# homie-wemos.net
KiCad netlist of a schematic drawn in EAGLE
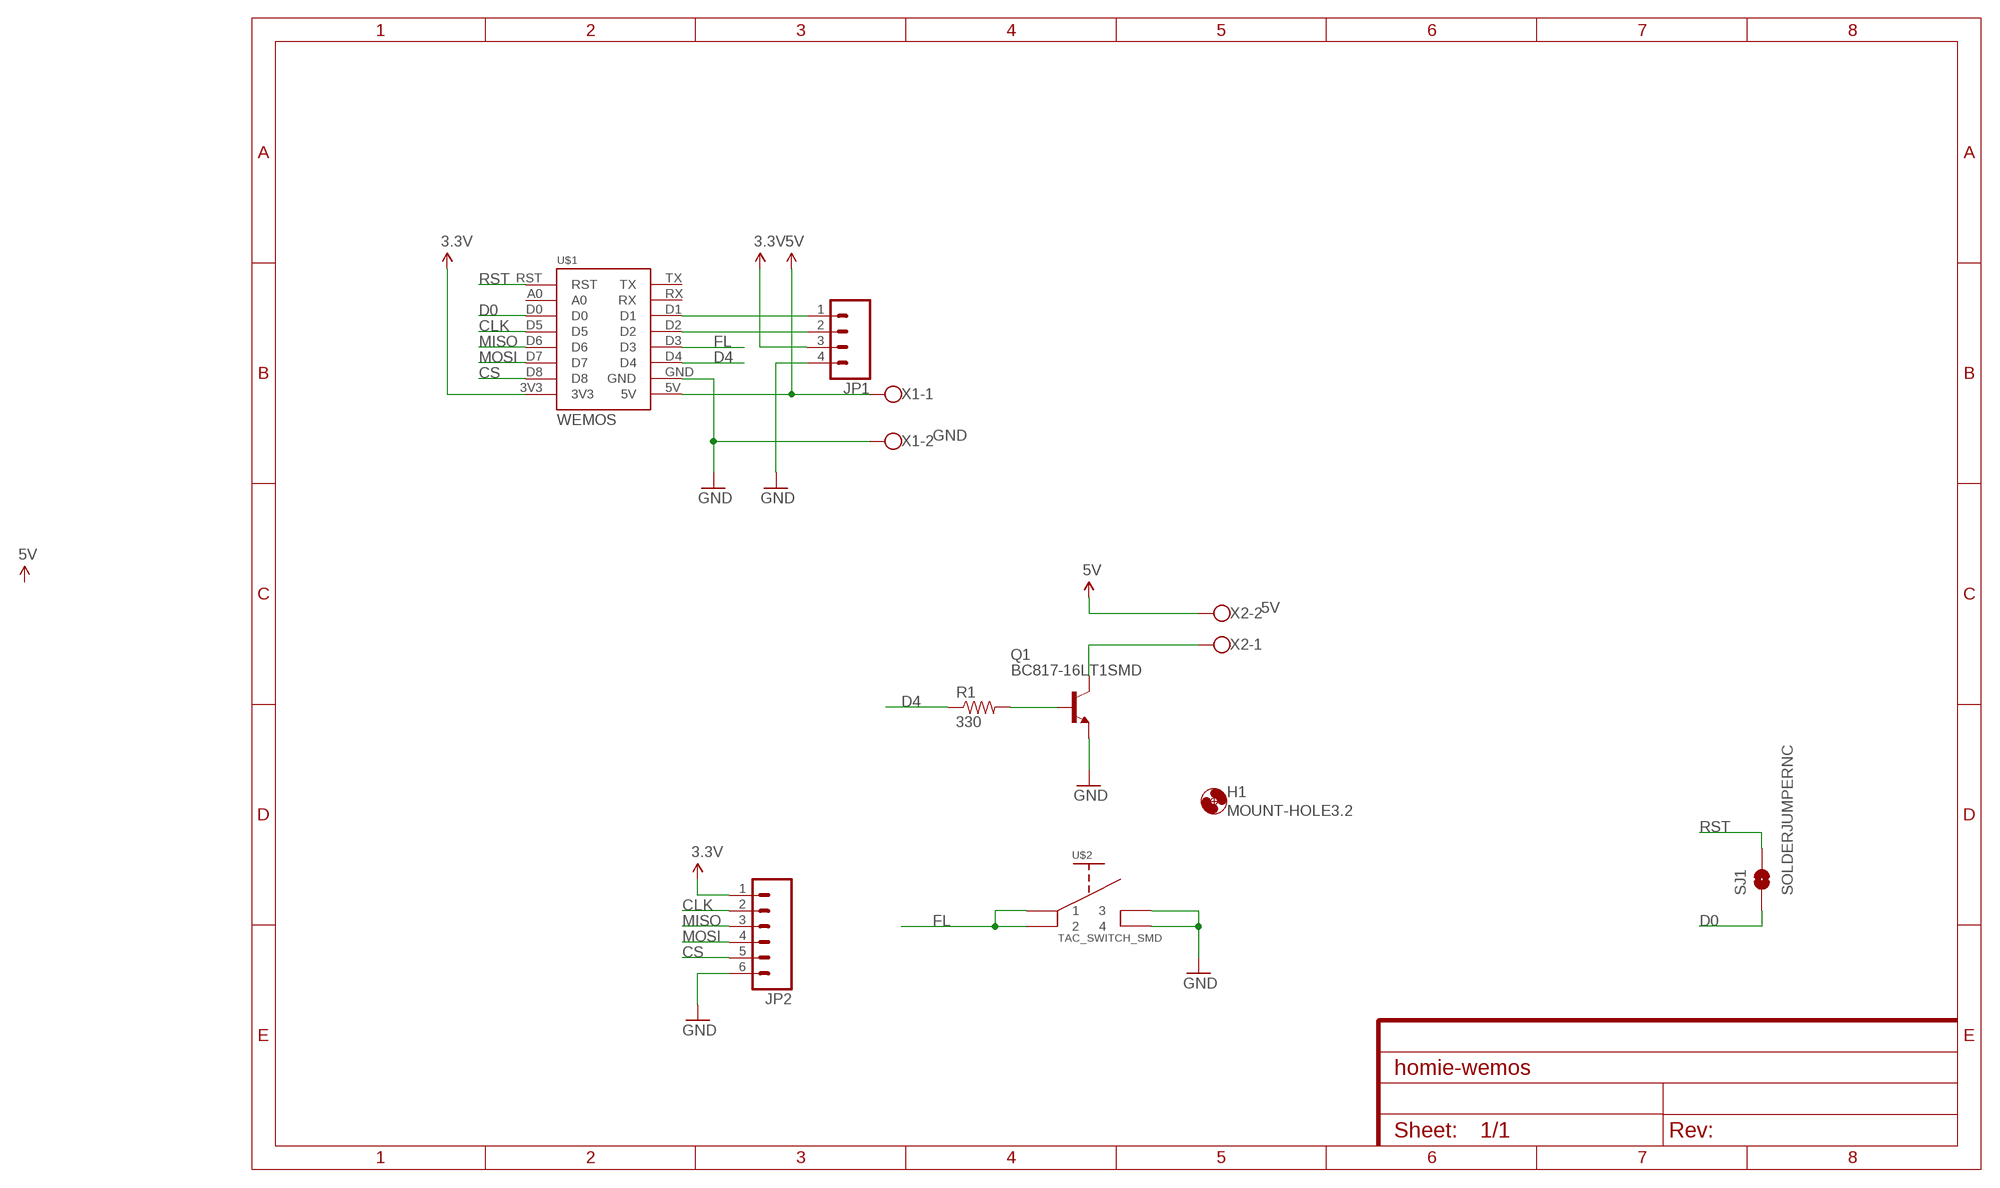
[diagram p0: schematic, sheet 1]

(export (version "E")
  (design (tool "Eeschema 10.0.6"))
  (components
    (comp (ref "H1")
      (value "MOUNT-HOLE3.2")
      (footprint "eagle-import:3,2")
      (libsource (lib "eagle-import") (part "MOUNT-HOLE3.2"))
    )
    (comp (ref "JP1")
      (value "M04LOCK_LONGPADS")
      (footprint "eagle-import:1X04_LOCK_LONGPADS")
      (libsource (lib "eagle-import") (part "M04LOCK_LONGPADS"))
    )
    (comp (ref "JP2")
      (value "M06LOCK_LONGPADS")
      (footprint "eagle-import:1X06_LOCK_LONGPADS")
      (libsource (lib "eagle-import") (part "M06LOCK_LONGPADS"))
    )
    (comp (ref "Q1")
      (value "BC817-16LT1SMD")
      (footprint "eagle-import:SOT23-BEC")
      (libsource (lib "eagle-import") (part "BC817SMD-16LT1"))
    )
    (comp (ref "R1")
      (value "330")
      (footprint "eagle-import:0603-RES")
      (libsource (lib "eagle-import") (part "RESISTOR0603-RES"))
    )
    (comp (ref "SJ1")
      (value "SOLDERJUMPERNC")
      (footprint "eagle-import:SJ_2S")
      (libsource (lib "eagle-import") (part "SOLDERJUMPERNC"))
    )
    (comp (ref "U$1")
      (value "WEMOS")
      (footprint "eagle-import:WEMOS")
      (libsource (lib "eagle-import") (part "WEMOS"))
    )
    (comp (ref "U$2")
      (value "TS-017A")
      (footprint "eagle-import:TS-017ASMD")
      (libsource (lib "eagle-import") (part "TS-017A"))
    )
    (comp (ref "X1")
      (value "W237-102")
      (footprint "eagle-import:W237-102")
      (fields (field (name "MPN") "237-102"))
      (libsource (lib "eagle-import") (part "W237-102"))
    )
    (comp (ref "X2")
      (value "W237-102")
      (footprint "eagle-import:W237-102")
      (fields (field (name "MPN") "237-102"))
      (libsource (lib "eagle-import") (part "W237-102"))
    )
  )
  (nets
    (net (code "1") (name "/CLK") (class "Default")
      (node (ref "JP2") (pin "2") (pinfunction "2_2") (pintype "passive"))
      (node (ref "U$1") (pin "D5") (pinfunction "D5_D5") (pintype "bidirectional"))
    )
    (net (code "2") (name "/CS") (class "Default")
      (node (ref "JP2") (pin "5") (pinfunction "5_5") (pintype "passive"))
      (node (ref "U$1") (pin "D8") (pinfunction "D8_D8") (pintype "bidirectional"))
    )
    (net (code "3") (name "/D0") (class "Default")
      (node (ref "SJ1") (pin "1") (pinfunction "1_1") (pintype "passive"))
      (node (ref "U$1") (pin "D0") (pinfunction "D0_D0") (pintype "bidirectional"))
    )
    (net (code "4") (name "/D4") (class "Default")
      (node (ref "R1") (pin "1") (pinfunction "1_1") (pintype "passive"))
      (node (ref "U$1") (pin "D4") (pinfunction "D4_D4") (pintype "bidirectional"))
    )
    (net (code "5") (name "/FL") (class "Default")
      (node (ref "U$1") (pin "D3") (pinfunction "D3_D3") (pintype "bidirectional"))
      (node (ref "U$2") (pin "P$1") (pinfunction "1_P$1") (pintype "bidirectional"))
      (node (ref "U$2") (pin "P$2") (pinfunction "2_P$2") (pintype "bidirectional"))
    )
    (net (code "6") (name "/MISO") (class "Default")
      (node (ref "JP2") (pin "3") (pinfunction "3_3") (pintype "passive"))
      (node (ref "U$1") (pin "D6") (pinfunction "D6_D6") (pintype "bidirectional"))
    )
    (net (code "7") (name "/MOSI") (class "Default")
      (node (ref "JP2") (pin "4") (pinfunction "4_4") (pintype "passive"))
      (node (ref "U$1") (pin "D7") (pinfunction "D7_D7") (pintype "bidirectional"))
    )
    (net (code "8") (name "/RST") (class "Default")
      (node (ref "SJ1") (pin "2") (pinfunction "2_2") (pintype "passive"))
      (node (ref "U$1") (pin "RST") (pinfunction "RST_RST") (pintype "bidirectional"))
    )
    (net (code "9") (name "3.3V") (class "Default")
      (node (ref "JP1") (pin "3") (pinfunction "3_3") (pintype "passive"))
      (node (ref "JP2") (pin "1") (pinfunction "1_1") (pintype "passive"))
      (node (ref "U$1") (pin "3V3") (pinfunction "3V3_3V3") (pintype "bidirectional"))
    )
    (net (code "10") (name "5V") (class "Default")
      (node (ref "U$1") (pin "5V") (pinfunction "5V_5V") (pintype "bidirectional"))
      (node (ref "X1") (pin "1") (pinfunction "KL_1") (pintype "passive"))
      (node (ref "X2") (pin "2") (pinfunction "KL_2") (pintype "passive"))
    )
    (net (code "11") (name "GND") (class "Default")
      (node (ref "JP1") (pin "4") (pinfunction "4_4") (pintype "passive"))
      (node (ref "JP2") (pin "6") (pinfunction "6_6") (pintype "passive"))
      (node (ref "Q1") (pin "E") (pinfunction "E_E") (pintype "passive"))
      (node (ref "U$1") (pin "GND") (pinfunction "GND_GND") (pintype "bidirectional"))
      (node (ref "U$2") (pin "P$3") (pinfunction "3_P$3") (pintype "bidirectional"))
      (node (ref "U$2") (pin "P$4") (pinfunction "4_P$4") (pintype "bidirectional"))
      (node (ref "X1") (pin "2") (pinfunction "KL_2") (pintype "passive"))
    )
    (net (code "12") (name "Net-(JP1-Pad1)") (class "Default")
      (node (ref "JP1") (pin "1") (pinfunction "1_1") (pintype "passive"))
      (node (ref "U$1") (pin "D1") (pinfunction "D1_D1") (pintype "bidirectional"))
    )
    (net (code "13") (name "Net-(JP1-Pad2)") (class "Default")
      (node (ref "JP1") (pin "2") (pinfunction "2_2") (pintype "passive"))
      (node (ref "U$1") (pin "D2") (pinfunction "D2_D2") (pintype "bidirectional"))
    )
    (net (code "14") (name "Net-(Q1-PadB)") (class "Default")
      (node (ref "Q1") (pin "B") (pinfunction "B_B") (pintype "passive"))
      (node (ref "R1") (pin "2") (pinfunction "2_2") (pintype "passive"))
    )
    (net (code "15") (name "Net-(X2A-KL)") (class "Default")
      (node (ref "Q1") (pin "C") (pinfunction "C_C") (pintype "passive"))
      (node (ref "X2") (pin "1") (pinfunction "KL_1") (pintype "passive"))
    )
    (net (code "16") (name "unconnected-(U$1-PadA0)") (class "Default")
      (node (ref "U$1") (pin "A0") (pinfunction "A0_A0") (pintype "bidirectional"))
    )
    (net (code "17") (name "unconnected-(U$1-PadRX)") (class "Default")
      (node (ref "U$1") (pin "RX") (pinfunction "RX_RX") (pintype "bidirectional"))
    )
    (net (code "18") (name "unconnected-(U$1-PadTX)") (class "Default")
      (node (ref "U$1") (pin "TX") (pinfunction "TX_TX") (pintype "bidirectional"))
    )
  )
)
